# CCHub_Breakout.net
KiCad netlist of a schematic drawn in Altium Designer
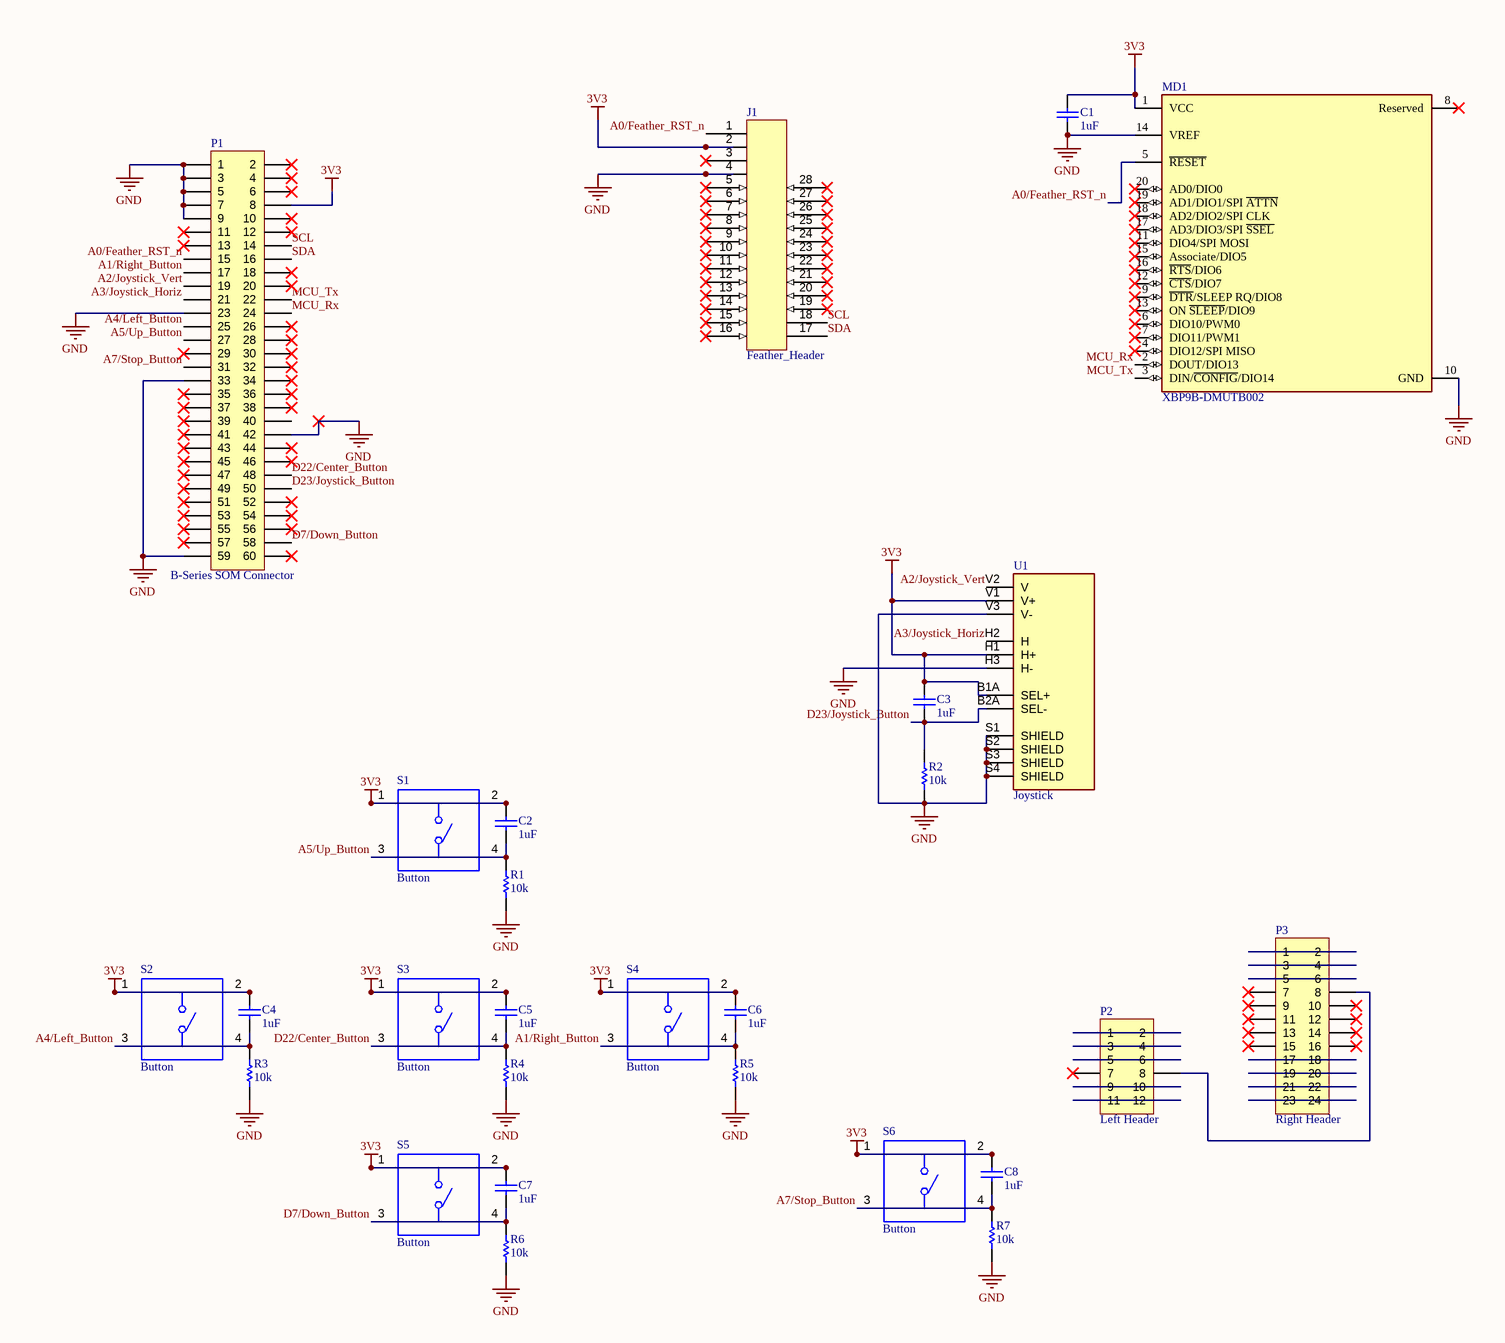
[diagram p0: CCHub Breakout.SchDoc]

(export (version "E")
  (design (tool "Eeschema 10.0.6"))
  (components
    (comp (ref "C1")
      (value "1uF")
      (footprint "1206 Capacitor")
      (description "Capacitor")
      (libsource (lib "Simulation Generic Components") (part "Capacitor"))
    )
    (comp (ref "C2")
      (value "1uF")
      (footprint "1206 Capacitor")
      (description "Capacitor")
      (libsource (lib "Simulation Generic Components") (part "Capacitor"))
    )
    (comp (ref "C3")
      (value "1uF")
      (footprint "1206 Capacitor")
      (description "Capacitor")
      (libsource (lib "Simulation Generic Components") (part "Capacitor"))
    )
    (comp (ref "C4")
      (value "1uF")
      (footprint "1206 Capacitor")
      (description "Capacitor")
      (libsource (lib "Simulation Generic Components") (part "Capacitor"))
    )
    (comp (ref "C5")
      (value "1uF")
      (footprint "1206 Capacitor")
      (description "Capacitor")
      (libsource (lib "Simulation Generic Components") (part "Capacitor"))
    )
    (comp (ref "C6")
      (value "1uF")
      (footprint "1206 Capacitor")
      (description "Capacitor")
      (libsource (lib "Simulation Generic Components") (part "Capacitor"))
    )
    (comp (ref "C7")
      (value "1uF")
      (footprint "1206 Capacitor")
      (description "Capacitor")
      (libsource (lib "Simulation Generic Components") (part "Capacitor"))
    )
    (comp (ref "C8")
      (value "1uF")
      (footprint "1206 Capacitor")
      (description "Capacitor")
      (libsource (lib "Simulation Generic Components") (part "Capacitor"))
    )
    (comp (ref "J1")
      (value "Feather_Header")
      (footprint "Feather_OLED")
      (libsource (lib "CCHUB_Symbols") (part "Feather_Header"))
    )
    (comp (ref "MD1")
      (value "XBP9B-DMUTB002")
      (footprint "FP-XBP9B-DMUTB002-MFG")
      (description "RX TXRX MOD ISM < 1GHZ U.FL TH")
      (libsource (lib "Altium Content Vault") (part "053d8e65a610ce00d52093c0e212ca3"))
    )
    (comp (ref "P1")
      (value "B-Series SOM Connector")
      (footprint "HDR2X30")
      (description "Header, 30-Pin, Dual row")
      (fields (field (name "PUBLISHER") "Altium Limited"))
      (libsource (lib "Miscellaneous Connectors") (part "Header 30X2"))
    )
    (comp (ref "P2")
      (value "Left Header")
      (footprint "HDR2X6")
      (description "Header, 6-Pin, Dual row")
      (fields (field (name "PUBLISHER") "Altium Limited"))
      (libsource (lib "Miscellaneous Connectors") (part "Header 6X2"))
    )
    (comp (ref "P3")
      (value "Right Header")
      (footprint "HDR2X12")
      (description "Header, 12-Pin, Dual row")
      (fields (field (name "PUBLISHER") "Altium Limited"))
      (libsource (lib "Miscellaneous Connectors") (part "Header 12X2"))
    )
    (comp (ref "R1")
      (value "10k")
      (footprint "1206 Resistor")
      (description "Resistor")
      (libsource (lib "Simulation Generic Components") (part "Resistor"))
    )
    (comp (ref "R2")
      (value "10k")
      (footprint "1206 Resistor")
      (description "Resistor")
      (libsource (lib "Simulation Generic Components") (part "Resistor"))
    )
    (comp (ref "R3")
      (value "10k")
      (footprint "1206 Resistor")
      (description "Resistor")
      (libsource (lib "Simulation Generic Components") (part "Resistor"))
    )
    (comp (ref "R4")
      (value "10k")
      (footprint "1206 Resistor")
      (description "Resistor")
      (libsource (lib "Simulation Generic Components") (part "Resistor"))
    )
    (comp (ref "R5")
      (value "10k")
      (footprint "1206 Resistor")
      (description "Resistor")
      (libsource (lib "Simulation Generic Components") (part "Resistor"))
    )
    (comp (ref "R6")
      (value "10k")
      (footprint "1206 Resistor")
      (description "Resistor")
      (libsource (lib "Simulation Generic Components") (part "Resistor"))
    )
    (comp (ref "R7")
      (value "10k")
      (footprint "1206 Resistor")
      (description "Resistor")
      (libsource (lib "Simulation Generic Components") (part "Resistor"))
    )
    (comp (ref "S1")
      (value "Button")
      (footprint "Makerspace Button")
      (description "6 x 6 mm, 17 mm Actuator Height, 260 gf, Black, Short Crimped, Through Hole, SPST, Tactile Switch")
      (fields (field (name "MP") "TS02-66-170-BK-260-SCR-D") (field (name "MF") "CUI Devices"))
      (libsource (lib "TS02-66-170-BK-260-SCR-D") (part "TS02-66-170-BK-260-SCR-D"))
    )
    (comp (ref "S2")
      (value "Button")
      (footprint "Makerspace Button")
      (description "6 x 6 mm, 17 mm Actuator Height, 260 gf, Black, Short Crimped, Through Hole, SPST, Tactile Switch")
      (fields (field (name "MP") "TS02-66-170-BK-260-SCR-D") (field (name "MF") "CUI Devices"))
      (libsource (lib "TS02-66-170-BK-260-SCR-D") (part "TS02-66-170-BK-260-SCR-D"))
    )
    (comp (ref "S3")
      (value "Button")
      (footprint "Makerspace Button")
      (description "6 x 6 mm, 17 mm Actuator Height, 260 gf, Black, Short Crimped, Through Hole, SPST, Tactile Switch")
      (fields (field (name "MP") "TS02-66-170-BK-260-SCR-D") (field (name "MF") "CUI Devices"))
      (libsource (lib "TS02-66-170-BK-260-SCR-D") (part "TS02-66-170-BK-260-SCR-D"))
    )
    (comp (ref "S4")
      (value "Button")
      (footprint "Makerspace Button")
      (description "6 x 6 mm, 17 mm Actuator Height, 260 gf, Black, Short Crimped, Through Hole, SPST, Tactile Switch")
      (fields (field (name "MP") "TS02-66-170-BK-260-SCR-D") (field (name "MF") "CUI Devices"))
      (libsource (lib "TS02-66-170-BK-260-SCR-D") (part "TS02-66-170-BK-260-SCR-D"))
    )
    (comp (ref "S5")
      (value "Button")
      (footprint "Makerspace Button")
      (description "6 x 6 mm, 17 mm Actuator Height, 260 gf, Black, Short Crimped, Through Hole, SPST, Tactile Switch")
      (fields (field (name "MP") "TS02-66-170-BK-260-SCR-D") (field (name "MF") "CUI Devices"))
      (libsource (lib "TS02-66-170-BK-260-SCR-D") (part "TS02-66-170-BK-260-SCR-D"))
    )
    (comp (ref "S6")
      (value "Button")
      (footprint "Makerspace Button")
      (description "6 x 6 mm, 17 mm Actuator Height, 260 gf, Black, Short Crimped, Through Hole, SPST, Tactile Switch")
      (fields (field (name "MP") "TS02-66-170-BK-260-SCR-D") (field (name "MF") "CUI Devices"))
      (libsource (lib "TS02-66-170-BK-260-SCR-D") (part "TS02-66-170-BK-260-SCR-D"))
    )
    (comp (ref "U1")
      (value "Joystick")
      (footprint "XDCR_COM-09032")
      (description "Thumb Joystick")
      (fields (field (name "MP") "COM-09032"))
      (libsource (lib "COM-09032") (part "COM-09032"))
    )
  )
  (nets
    (net (code "1") (name "/A0{slash}Feather_RST_n") (class "Default")
      (node (ref "J1") (pin "1") (pintype "passive"))
      (node (ref "MD1") (pin "5") (pinfunction "~{RESET}_5") (pintype "passive"))
      (node (ref "P1") (pin "15") (pinfunction "15_15") (pintype "passive"))
    )
    (net (code "2") (name "/A1{slash}Right_Button") (class "Default")
      (node (ref "C6") (pin "1") (pinfunction "1_1") (pintype "passive"))
      (node (ref "P1") (pin "17") (pinfunction "17_17") (pintype "passive"))
      (node (ref "R5") (pin "2") (pinfunction "2_2") (pintype "passive"))
      (node (ref "S4") (pin "3") (pinfunction "3_3") (pintype "passive"))
      (node (ref "S4") (pin "4") (pinfunction "4_4") (pintype "passive"))
    )
    (net (code "3") (name "/A2{slash}Joystick_Vert") (class "Default")
      (node (ref "P1") (pin "19") (pinfunction "19_19") (pintype "passive"))
      (node (ref "U1") (pin "V2") (pinfunction "V_V2") (pintype "passive"))
    )
    (net (code "4") (name "/A3{slash}Joystick_Horiz") (class "Default")
      (node (ref "P1") (pin "21") (pinfunction "21_21") (pintype "passive"))
      (node (ref "U1") (pin "H2") (pinfunction "H_H2") (pintype "passive"))
    )
    (net (code "5") (name "/A4{slash}Left_Button") (class "Default")
      (node (ref "C4") (pin "1") (pinfunction "1_1") (pintype "passive"))
      (node (ref "P1") (pin "25") (pinfunction "25_25") (pintype "passive"))
      (node (ref "R3") (pin "2") (pinfunction "2_2") (pintype "passive"))
      (node (ref "S2") (pin "3") (pinfunction "3_3") (pintype "passive"))
      (node (ref "S2") (pin "4") (pinfunction "4_4") (pintype "passive"))
    )
    (net (code "6") (name "/A5{slash}Up_Button") (class "Default")
      (node (ref "C2") (pin "1") (pinfunction "1_1") (pintype "passive"))
      (node (ref "P1") (pin "27") (pinfunction "27_27") (pintype "passive"))
      (node (ref "R1") (pin "2") (pinfunction "2_2") (pintype "passive"))
      (node (ref "S1") (pin "3") (pinfunction "3_3") (pintype "passive"))
      (node (ref "S1") (pin "4") (pinfunction "4_4") (pintype "passive"))
    )
    (net (code "7") (name "/A7{slash}Stop_Button") (class "Default")
      (node (ref "C8") (pin "1") (pinfunction "1_1") (pintype "passive"))
      (node (ref "P1") (pin "31") (pinfunction "31_31") (pintype "passive"))
      (node (ref "R7") (pin "2") (pinfunction "2_2") (pintype "passive"))
      (node (ref "S6") (pin "3") (pinfunction "3_3") (pintype "passive"))
      (node (ref "S6") (pin "4") (pinfunction "4_4") (pintype "passive"))
    )
    (net (code "8") (name "/D7{slash}Down_Button") (class "Default")
      (node (ref "C7") (pin "1") (pinfunction "1_1") (pintype "passive"))
      (node (ref "P1") (pin "58") (pinfunction "58_58") (pintype "passive"))
      (node (ref "R6") (pin "2") (pinfunction "2_2") (pintype "passive"))
      (node (ref "S5") (pin "3") (pinfunction "3_3") (pintype "passive"))
      (node (ref "S5") (pin "4") (pinfunction "4_4") (pintype "passive"))
    )
    (net (code "9") (name "/D22{slash}Center_Button") (class "Default")
      (node (ref "C5") (pin "1") (pinfunction "1_1") (pintype "passive"))
      (node (ref "P1") (pin "48") (pinfunction "48_48") (pintype "passive"))
      (node (ref "R4") (pin "2") (pinfunction "2_2") (pintype "passive"))
      (node (ref "S3") (pin "3") (pinfunction "3_3") (pintype "passive"))
      (node (ref "S3") (pin "4") (pinfunction "4_4") (pintype "passive"))
    )
    (net (code "10") (name "/D23{slash}Joystick_Button") (class "Default")
      (node (ref "C3") (pin "1") (pinfunction "1_1") (pintype "passive"))
      (node (ref "P1") (pin "50") (pinfunction "50_50") (pintype "passive"))
      (node (ref "R2") (pin "2") (pinfunction "2_2") (pintype "passive"))
      (node (ref "U1") (pin "B2A") (pinfunction "SEL-_B2A") (pintype "passive"))
    )
    (net (code "11") (name "/MCU_Rx") (class "Default")
      (node (ref "MD1") (pin "2") (pinfunction "DOUT/DIO13_2") (pintype "bidirectional"))
      (node (ref "P1") (pin "24") (pinfunction "24_24") (pintype "passive"))
    )
    (net (code "12") (name "/MCU_Tx") (class "Default")
      (node (ref "MD1") (pin "3") (pinfunction "DIN/~{CONFIG}/DIO14_3") (pintype "bidirectional"))
      (node (ref "P1") (pin "22") (pinfunction "22_22") (pintype "passive"))
    )
    (net (code "13") (name "/SCL") (class "Default")
      (node (ref "J1") (pin "18") (pintype "passive"))
      (node (ref "P1") (pin "14") (pinfunction "14_14") (pintype "passive"))
    )
    (net (code "14") (name "/SDA") (class "Default")
      (node (ref "J1") (pin "17") (pintype "passive"))
      (node (ref "P1") (pin "16") (pinfunction "16_16") (pintype "passive"))
    )
    (net (code "15") (name "3V3") (class "Default")
      (node (ref "C1") (pin "2") (pinfunction "2_2") (pintype "passive"))
      (node (ref "C2") (pin "2") (pinfunction "2_2") (pintype "passive"))
      (node (ref "C3") (pin "2") (pinfunction "2_2") (pintype "passive"))
      (node (ref "C4") (pin "2") (pinfunction "2_2") (pintype "passive"))
      (node (ref "C5") (pin "2") (pinfunction "2_2") (pintype "passive"))
      (node (ref "C6") (pin "2") (pinfunction "2_2") (pintype "passive"))
      (node (ref "C7") (pin "2") (pinfunction "2_2") (pintype "passive"))
      (node (ref "C8") (pin "2") (pinfunction "2_2") (pintype "passive"))
      (node (ref "J1") (pin "2") (pintype "passive"))
      (node (ref "MD1") (pin "1") (pinfunction "VCC_1") (pintype "power_in"))
      (node (ref "P1") (pin "8") (pinfunction "8_8") (pintype "passive"))
      (node (ref "S1") (pin "1") (pinfunction "1_1") (pintype "passive"))
      (node (ref "S1") (pin "2") (pinfunction "2_2") (pintype "passive"))
      (node (ref "S2") (pin "1") (pinfunction "1_1") (pintype "passive"))
      (node (ref "S2") (pin "2") (pinfunction "2_2") (pintype "passive"))
      (node (ref "S3") (pin "1") (pinfunction "1_1") (pintype "passive"))
      (node (ref "S3") (pin "2") (pinfunction "2_2") (pintype "passive"))
      (node (ref "S4") (pin "1") (pinfunction "1_1") (pintype "passive"))
      (node (ref "S4") (pin "2") (pinfunction "2_2") (pintype "passive"))
      (node (ref "S5") (pin "1") (pinfunction "1_1") (pintype "passive"))
      (node (ref "S5") (pin "2") (pinfunction "2_2") (pintype "passive"))
      (node (ref "S6") (pin "1") (pinfunction "1_1") (pintype "passive"))
      (node (ref "S6") (pin "2") (pinfunction "2_2") (pintype "passive"))
      (node (ref "U1") (pin "B1A") (pinfunction "SEL+_B1A") (pintype "passive"))
      (node (ref "U1") (pin "H1") (pinfunction "H+_H1") (pintype "passive"))
      (node (ref "U1") (pin "V1") (pinfunction "V+_V1") (pintype "passive"))
    )
    (net (code "16") (name "GND") (class "Default")
      (node (ref "C1") (pin "1") (pinfunction "1_1") (pintype "passive"))
      (node (ref "J1") (pin "4") (pintype "passive"))
      (node (ref "MD1") (pin "10") (pinfunction "GND_10") (pintype "power_in"))
      (node (ref "MD1") (pin "14") (pinfunction "VREF_14") (pintype "passive"))
      (node (ref "P1") (pin "1") (pinfunction "1_1") (pintype "passive"))
      (node (ref "P1") (pin "23") (pinfunction "23_23") (pintype "passive"))
      (node (ref "P1") (pin "3") (pinfunction "3_3") (pintype "passive"))
      (node (ref "P1") (pin "33") (pinfunction "33_33") (pintype "passive"))
      (node (ref "P1") (pin "42") (pinfunction "42_42") (pintype "passive"))
      (node (ref "P1") (pin "5") (pinfunction "5_5") (pintype "passive"))
      (node (ref "P1") (pin "59") (pinfunction "59_59") (pintype "passive"))
      (node (ref "P1") (pin "7") (pinfunction "7_7") (pintype "passive"))
      (node (ref "P1") (pin "9") (pinfunction "9_9") (pintype "passive"))
      (node (ref "R1") (pin "1") (pinfunction "1_1") (pintype "passive"))
      (node (ref "R2") (pin "1") (pinfunction "1_1") (pintype "passive"))
      (node (ref "R3") (pin "1") (pinfunction "1_1") (pintype "passive"))
      (node (ref "R4") (pin "1") (pinfunction "1_1") (pintype "passive"))
      (node (ref "R5") (pin "1") (pinfunction "1_1") (pintype "passive"))
      (node (ref "R6") (pin "1") (pinfunction "1_1") (pintype "passive"))
      (node (ref "R7") (pin "1") (pinfunction "1_1") (pintype "passive"))
      (node (ref "U1") (pin "H3") (pinfunction "H-_H3") (pintype "passive"))
      (node (ref "U1") (pin "S1") (pinfunction "SHIELD_S1") (pintype "passive"))
      (node (ref "U1") (pin "S2") (pinfunction "SHIELD_S2") (pintype "passive"))
      (node (ref "U1") (pin "S3") (pinfunction "SHIELD_S3") (pintype "passive"))
      (node (ref "U1") (pin "S4") (pinfunction "SHIELD_S4") (pintype "passive"))
      (node (ref "U1") (pin "V3") (pinfunction "V-_V3") (pintype "passive"))
    )
    (net (code "17") (name "Net-(P2-Pad1)") (class "Default")
      (node (ref "P2") (pin "1") (pinfunction "1_1") (pintype "passive"))
      (node (ref "P2") (pin "2") (pinfunction "2_2") (pintype "passive"))
    )
    (net (code "18") (name "Net-(P2-Pad3)") (class "Default")
      (node (ref "P2") (pin "3") (pinfunction "3_3") (pintype "passive"))
      (node (ref "P2") (pin "4") (pinfunction "4_4") (pintype "passive"))
    )
    (net (code "19") (name "Net-(P2-Pad5)") (class "Default")
      (node (ref "P2") (pin "5") (pinfunction "5_5") (pintype "passive"))
      (node (ref "P2") (pin "6") (pinfunction "6_6") (pintype "passive"))
    )
    (net (code "20") (name "Net-(P2-Pad8)") (class "Default")
      (node (ref "P2") (pin "8") (pinfunction "8_8") (pintype "passive"))
      (node (ref "P3") (pin "8") (pinfunction "8_8") (pintype "passive"))
    )
    (net (code "21") (name "Net-(P2-Pad10)") (class "Default")
      (node (ref "P2") (pin "10") (pinfunction "10_10") (pintype "passive"))
      (node (ref "P2") (pin "9") (pinfunction "9_9") (pintype "passive"))
    )
    (net (code "22") (name "Net-(P2-Pad11)") (class "Default")
      (node (ref "P2") (pin "11") (pinfunction "11_11") (pintype "passive"))
      (node (ref "P2") (pin "12") (pinfunction "12_12") (pintype "passive"))
    )
    (net (code "23") (name "Net-(P3-Pad1)") (class "Default")
      (node (ref "P3") (pin "1") (pinfunction "1_1") (pintype "passive"))
      (node (ref "P3") (pin "2") (pinfunction "2_2") (pintype "passive"))
    )
    (net (code "24") (name "Net-(P3-Pad3)") (class "Default")
      (node (ref "P3") (pin "3") (pinfunction "3_3") (pintype "passive"))
      (node (ref "P3") (pin "4") (pinfunction "4_4") (pintype "passive"))
    )
    (net (code "25") (name "Net-(P3-Pad5)") (class "Default")
      (node (ref "P3") (pin "5") (pinfunction "5_5") (pintype "passive"))
      (node (ref "P3") (pin "6") (pinfunction "6_6") (pintype "passive"))
    )
    (net (code "26") (name "Net-(P3-Pad17)") (class "Default")
      (node (ref "P3") (pin "17") (pinfunction "17_17") (pintype "passive"))
      (node (ref "P3") (pin "18") (pinfunction "18_18") (pintype "passive"))
    )
    (net (code "27") (name "Net-(P3-Pad19)") (class "Default")
      (node (ref "P3") (pin "19") (pinfunction "19_19") (pintype "passive"))
      (node (ref "P3") (pin "20") (pinfunction "20_20") (pintype "passive"))
    )
    (net (code "28") (name "Net-(P3-Pad21)") (class "Default")
      (node (ref "P3") (pin "21") (pinfunction "21_21") (pintype "passive"))
      (node (ref "P3") (pin "22") (pinfunction "22_22") (pintype "passive"))
    )
    (net (code "29") (name "Net-(P3-Pad23)") (class "Default")
      (node (ref "P3") (pin "23") (pinfunction "23_23") (pintype "passive"))
      (node (ref "P3") (pin "24") (pinfunction "24_24") (pintype "passive"))
    )
    (net (code "30") (name "unconnected-(J1-Pad3)") (class "Default")
      (node (ref "J1") (pin "3") (pintype "passive+no_connect"))
    )
    (net (code "31") (name "unconnected-(J1-Pad5)") (class "Default")
      (node (ref "J1") (pin "5") (pintype "input+no_connect"))
    )
    (net (code "32") (name "unconnected-(J1-Pad6)") (class "Default")
      (node (ref "J1") (pin "6") (pintype "input+no_connect"))
    )
    (net (code "33") (name "unconnected-(J1-Pad7)") (class "Default")
      (node (ref "J1") (pin "7") (pintype "input+no_connect"))
    )
    (net (code "34") (name "unconnected-(J1-Pad8)") (class "Default")
      (node (ref "J1") (pin "8") (pintype "input+no_connect"))
    )
    (net (code "35") (name "unconnected-(J1-Pad9)") (class "Default")
      (node (ref "J1") (pin "9") (pintype "input+no_connect"))
    )
    (net (code "36") (name "unconnected-(J1-Pad10)") (class "Default")
      (node (ref "J1") (pin "10") (pintype "input+no_connect"))
    )
    (net (code "37") (name "unconnected-(J1-Pad11)") (class "Default")
      (node (ref "J1") (pin "11") (pintype "input+no_connect"))
    )
    (net (code "38") (name "unconnected-(J1-Pad12)") (class "Default")
      (node (ref "J1") (pin "12") (pintype "input+no_connect"))
    )
    (net (code "39") (name "unconnected-(J1-Pad13)") (class "Default")
      (node (ref "J1") (pin "13") (pintype "input+no_connect"))
    )
    (net (code "40") (name "unconnected-(J1-Pad14)") (class "Default")
      (node (ref "J1") (pin "14") (pintype "input+no_connect"))
    )
    (net (code "41") (name "unconnected-(J1-Pad15)") (class "Default")
      (node (ref "J1") (pin "15") (pintype "input+no_connect"))
    )
    (net (code "42") (name "unconnected-(J1-Pad16)") (class "Default")
      (node (ref "J1") (pin "16") (pintype "input+no_connect"))
    )
    (net (code "43") (name "unconnected-(J1-Pad19)") (class "Default")
      (node (ref "J1") (pin "19") (pintype "input+no_connect"))
    )
    (net (code "44") (name "unconnected-(J1-Pad20)") (class "Default")
      (node (ref "J1") (pin "20") (pintype "input+no_connect"))
    )
    (net (code "45") (name "unconnected-(J1-Pad21)") (class "Default")
      (node (ref "J1") (pin "21") (pintype "input+no_connect"))
    )
    (net (code "46") (name "unconnected-(J1-Pad22)") (class "Default")
      (node (ref "J1") (pin "22") (pintype "input+no_connect"))
    )
    (net (code "47") (name "unconnected-(J1-Pad23)") (class "Default")
      (node (ref "J1") (pin "23") (pintype "input+no_connect"))
    )
    (net (code "48") (name "unconnected-(J1-Pad24)") (class "Default")
      (node (ref "J1") (pin "24") (pintype "input+no_connect"))
    )
    (net (code "49") (name "unconnected-(J1-Pad25)") (class "Default")
      (node (ref "J1") (pin "25") (pintype "input+no_connect"))
    )
    (net (code "50") (name "unconnected-(J1-Pad26)") (class "Default")
      (node (ref "J1") (pin "26") (pintype "input+no_connect"))
    )
    (net (code "51") (name "unconnected-(J1-Pad27)") (class "Default")
      (node (ref "J1") (pin "27") (pintype "input+no_connect"))
    )
    (net (code "52") (name "unconnected-(J1-Pad28)") (class "Default")
      (node (ref "J1") (pin "28") (pintype "input+no_connect"))
    )
    (net (code "53") (name "unconnected-(MD1-AD0{slash}DIO0-Pad20)") (class "Default")
      (node (ref "MD1") (pin "20") (pinfunction "AD0/DIO0_20") (pintype "bidirectional+no_connect"))
    )
    (net (code "54") (name "unconnected-(MD1-AD1{slash}DIO1{slash}SPI_~{ATTN}-Pad19)") (class "Default")
      (node (ref "MD1") (pin "19") (pinfunction "AD1/DIO1/SPI_~{ATTN}_19") (pintype "bidirectional+no_connect"))
    )
    (net (code "55") (name "unconnected-(MD1-AD2{slash}DIO2{slash}SPI_CLK-Pad18)") (class "Default")
      (node (ref "MD1") (pin "18") (pinfunction "AD2/DIO2/SPI_CLK_18") (pintype "bidirectional+no_connect"))
    )
    (net (code "56") (name "unconnected-(MD1-AD3{slash}DIO3{slash}SPI_~{SSEL}-Pad17)") (class "Default")
      (node (ref "MD1") (pin "17") (pinfunction "AD3/DIO3/SPI_~{SSEL}_17") (pintype "bidirectional+no_connect"))
    )
    (net (code "57") (name "unconnected-(MD1-Associate{slash}DIO5-Pad15)") (class "Default")
      (node (ref "MD1") (pin "15") (pinfunction "Associate/DIO5_15") (pintype "bidirectional+no_connect"))
    )
    (net (code "58") (name "unconnected-(MD1-DIO4{slash}SPI_MOSI-Pad11)") (class "Default")
      (node (ref "MD1") (pin "11") (pinfunction "DIO4/SPI_MOSI_11") (pintype "bidirectional+no_connect"))
    )
    (net (code "59") (name "unconnected-(MD1-DIO10{slash}PWM0-Pad6)") (class "Default")
      (node (ref "MD1") (pin "6") (pinfunction "DIO10/PWM0_6") (pintype "bidirectional+no_connect"))
    )
    (net (code "60") (name "unconnected-(MD1-DIO11{slash}PWM1-Pad7)") (class "Default")
      (node (ref "MD1") (pin "7") (pinfunction "DIO11/PWM1_7") (pintype "bidirectional+no_connect"))
    )
    (net (code "61") (name "unconnected-(MD1-DIO12{slash}SPI_MISO-Pad4)") (class "Default")
      (node (ref "MD1") (pin "4") (pinfunction "DIO12/SPI_MISO_4") (pintype "bidirectional+no_connect"))
    )
    (net (code "62") (name "unconnected-(MD1-ON_~{SLEEP}{slash}DIO9-Pad13)") (class "Default")
      (node (ref "MD1") (pin "13") (pinfunction "ON_~{SLEEP}/DIO9_13") (pintype "bidirectional+no_connect"))
    )
    (net (code "63") (name "unconnected-(MD1-Reserved-Pad8)") (class "Default")
      (node (ref "MD1") (pin "8") (pinfunction "Reserved_8") (pintype "passive+no_connect"))
    )
    (net (code "64") (name "unconnected-(MD1-~{CTS}{slash}DIO7-Pad12)") (class "Default")
      (node (ref "MD1") (pin "12") (pinfunction "~{CTS}/DIO7_12") (pintype "bidirectional+no_connect"))
    )
    (net (code "65") (name "unconnected-(MD1-~{DTR}{slash}SLEEP_RQ{slash}DIO8-Pad9)") (class "Default")
      (node (ref "MD1") (pin "9") (pinfunction "~{DTR}/SLEEP_RQ/DIO8_9") (pintype "bidirectional+no_connect"))
    )
    (net (code "66") (name "unconnected-(MD1-~{RTS}{slash}DIO6-Pad16)") (class "Default")
      (node (ref "MD1") (pin "16") (pinfunction "~{RTS}/DIO6_16") (pintype "bidirectional+no_connect"))
    )
    (net (code "67") (name "unconnected-(P1-Pad2)") (class "Default")
      (node (ref "P1") (pin "2") (pinfunction "2_2") (pintype "passive+no_connect"))
    )
    (net (code "68") (name "unconnected-(P1-Pad4)") (class "Default")
      (node (ref "P1") (pin "4") (pinfunction "4_4") (pintype "passive+no_connect"))
    )
    (net (code "69") (name "unconnected-(P1-Pad6)") (class "Default")
      (node (ref "P1") (pin "6") (pinfunction "6_6") (pintype "passive+no_connect"))
    )
    (net (code "70") (name "unconnected-(P1-Pad10)") (class "Default")
      (node (ref "P1") (pin "10") (pinfunction "10_10") (pintype "passive+no_connect"))
    )
    (net (code "71") (name "unconnected-(P1-Pad11)") (class "Default")
      (node (ref "P1") (pin "11") (pinfunction "11_11") (pintype "passive+no_connect"))
    )
    (net (code "72") (name "unconnected-(P1-Pad12)") (class "Default")
      (node (ref "P1") (pin "12") (pinfunction "12_12") (pintype "passive+no_connect"))
    )
    (net (code "73") (name "unconnected-(P1-Pad13)") (class "Default")
      (node (ref "P1") (pin "13") (pinfunction "13_13") (pintype "passive+no_connect"))
    )
    (net (code "74") (name "unconnected-(P1-Pad18)") (class "Default")
      (node (ref "P1") (pin "18") (pinfunction "18_18") (pintype "passive+no_connect"))
    )
    (net (code "75") (name "unconnected-(P1-Pad20)") (class "Default")
      (node (ref "P1") (pin "20") (pinfunction "20_20") (pintype "passive+no_connect"))
    )
    (net (code "76") (name "unconnected-(P1-Pad26)") (class "Default")
      (node (ref "P1") (pin "26") (pinfunction "26_26") (pintype "passive+no_connect"))
    )
    (net (code "77") (name "unconnected-(P1-Pad28)") (class "Default")
      (node (ref "P1") (pin "28") (pinfunction "28_28") (pintype "passive+no_connect"))
    )
    (net (code "78") (name "unconnected-(P1-Pad29)") (class "Default")
      (node (ref "P1") (pin "29") (pinfunction "29_29") (pintype "passive+no_connect"))
    )
    (net (code "79") (name "unconnected-(P1-Pad30)") (class "Default")
      (node (ref "P1") (pin "30") (pinfunction "30_30") (pintype "passive+no_connect"))
    )
    (net (code "80") (name "unconnected-(P1-Pad32)") (class "Default")
      (node (ref "P1") (pin "32") (pinfunction "32_32") (pintype "passive+no_connect"))
    )
    (net (code "81") (name "unconnected-(P1-Pad34)") (class "Default")
      (node (ref "P1") (pin "34") (pinfunction "34_34") (pintype "passive+no_connect"))
    )
    (net (code "82") (name "unconnected-(P1-Pad35)") (class "Default")
      (node (ref "P1") (pin "35") (pinfunction "35_35") (pintype "passive+no_connect"))
    )
    (net (code "83") (name "unconnected-(P1-Pad36)") (class "Default")
      (node (ref "P1") (pin "36") (pinfunction "36_36") (pintype "passive+no_connect"))
    )
    (net (code "84") (name "unconnected-(P1-Pad37)") (class "Default")
      (node (ref "P1") (pin "37") (pinfunction "37_37") (pintype "passive+no_connect"))
    )
    (net (code "85") (name "unconnected-(P1-Pad38)") (class "Default")
      (node (ref "P1") (pin "38") (pinfunction "38_38") (pintype "passive+no_connect"))
    )
    (net (code "86") (name "unconnected-(P1-Pad39)") (class "Default")
      (node (ref "P1") (pin "39") (pinfunction "39_39") (pintype "passive+no_connect"))
    )
    (net (code "87") (name "unconnected-(P1-Pad40)") (class "Default")
      (node (ref "P1") (pin "40") (pinfunction "40_40") (pintype "passive"))
    )
    (net (code "88") (name "unconnected-(P1-Pad41)") (class "Default")
      (node (ref "P1") (pin "41") (pinfunction "41_41") (pintype "passive+no_connect"))
    )
    (net (code "89") (name "unconnected-(P1-Pad43)") (class "Default")
      (node (ref "P1") (pin "43") (pinfunction "43_43") (pintype "passive+no_connect"))
    )
    (net (code "90") (name "unconnected-(P1-Pad44)") (class "Default")
      (node (ref "P1") (pin "44") (pinfunction "44_44") (pintype "passive+no_connect"))
    )
    (net (code "91") (name "unconnected-(P1-Pad45)") (class "Default")
      (node (ref "P1") (pin "45") (pinfunction "45_45") (pintype "passive+no_connect"))
    )
    (net (code "92") (name "unconnected-(P1-Pad46)") (class "Default")
      (node (ref "P1") (pin "46") (pinfunction "46_46") (pintype "passive+no_connect"))
    )
    (net (code "93") (name "unconnected-(P1-Pad47)") (class "Default")
      (node (ref "P1") (pin "47") (pinfunction "47_47") (pintype "passive+no_connect"))
    )
    (net (code "94") (name "unconnected-(P1-Pad49)") (class "Default")
      (node (ref "P1") (pin "49") (pinfunction "49_49") (pintype "passive+no_connect"))
    )
    (net (code "95") (name "unconnected-(P1-Pad51)") (class "Default")
      (node (ref "P1") (pin "51") (pinfunction "51_51") (pintype "passive+no_connect"))
    )
    (net (code "96") (name "unconnected-(P1-Pad52)") (class "Default")
      (node (ref "P1") (pin "52") (pinfunction "52_52") (pintype "passive+no_connect"))
    )
    (net (code "97") (name "unconnected-(P1-Pad53)") (class "Default")
      (node (ref "P1") (pin "53") (pinfunction "53_53") (pintype "passive+no_connect"))
    )
    (net (code "98") (name "unconnected-(P1-Pad54)") (class "Default")
      (node (ref "P1") (pin "54") (pinfunction "54_54") (pintype "passive+no_connect"))
    )
    (net (code "99") (name "unconnected-(P1-Pad55)") (class "Default")
      (node (ref "P1") (pin "55") (pinfunction "55_55") (pintype "passive+no_connect"))
    )
    (net (code "100") (name "unconnected-(P1-Pad56)") (class "Default")
      (node (ref "P1") (pin "56") (pinfunction "56_56") (pintype "passive+no_connect"))
    )
    (net (code "101") (name "unconnected-(P1-Pad57)") (class "Default")
      (node (ref "P1") (pin "57") (pinfunction "57_57") (pintype "passive+no_connect"))
    )
    (net (code "102") (name "unconnected-(P1-Pad60)") (class "Default")
      (node (ref "P1") (pin "60") (pinfunction "60_60") (pintype "passive+no_connect"))
    )
    (net (code "103") (name "unconnected-(P2-Pad7)") (class "Default")
      (node (ref "P2") (pin "7") (pinfunction "7_7") (pintype "passive+no_connect"))
    )
    (net (code "104") (name "unconnected-(P3-Pad7)") (class "Default")
      (node (ref "P3") (pin "7") (pinfunction "7_7") (pintype "passive+no_connect"))
    )
    (net (code "105") (name "unconnected-(P3-Pad9)") (class "Default")
      (node (ref "P3") (pin "9") (pinfunction "9_9") (pintype "passive+no_connect"))
    )
    (net (code "106") (name "unconnected-(P3-Pad10)") (class "Default")
      (node (ref "P3") (pin "10") (pinfunction "10_10") (pintype "passive+no_connect"))
    )
    (net (code "107") (name "unconnected-(P3-Pad11)") (class "Default")
      (node (ref "P3") (pin "11") (pinfunction "11_11") (pintype "passive+no_connect"))
    )
    (net (code "108") (name "unconnected-(P3-Pad12)") (class "Default")
      (node (ref "P3") (pin "12") (pinfunction "12_12") (pintype "passive+no_connect"))
    )
    (net (code "109") (name "unconnected-(P3-Pad13)") (class "Default")
      (node (ref "P3") (pin "13") (pinfunction "13_13") (pintype "passive+no_connect"))
    )
    (net (code "110") (name "unconnected-(P3-Pad14)") (class "Default")
      (node (ref "P3") (pin "14") (pinfunction "14_14") (pintype "passive+no_connect"))
    )
    (net (code "111") (name "unconnected-(P3-Pad15)") (class "Default")
      (node (ref "P3") (pin "15") (pinfunction "15_15") (pintype "passive+no_connect"))
    )
    (net (code "112") (name "unconnected-(P3-Pad16)") (class "Default")
      (node (ref "P3") (pin "16") (pinfunction "16_16") (pintype "passive+no_connect"))
    )
  )
)
